# LoraRFM.net
KiCad netlist of a schematic drawn in Altium Designer
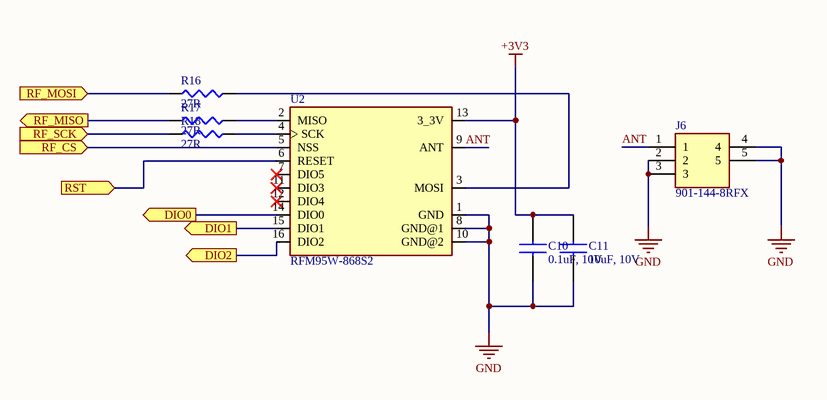
[diagram p0: LoraRFM.SchDoc]

(export (version "E")
  (design (tool "Eeschema 10.0.6"))
  (components
    (comp (ref "C10")
      (value "0.1uF, 10V")
      (footprint "SamacSys:CAPC1608X90N")
      (description "CAP CER 0.1UF 10V X7R 0603")
      (fields
        (field (name "MANUFACTURER_PART_NUMBER") "C0603C104K8RACTU")
        (field (name "MOUSER PART NUMBER") "187-CL10A106MP8NNNC")
      )
      (libsource (lib "SchlibpolyESP") (part "C0603C104K8RACTU"))
    )
    (comp (ref "C11")
      (value "10uF, 10V")
      (footprint "SamacSys:CAPC1608X90N")
      (description "CAP CER 10UF 10V X5R 0603")
      (fields
        (field (name "MANUFACTURER_PART_NUMBER") "CL10A106MP8NNNC")
        (field (name "MOUSER PART NUMBER") "187-CL10A106MP8NNNC")
      )
      (libsource (lib "SchlibpolyESP") (part "CL10A106MP8NNNC"))
    )
    (comp (ref "J6")
      (value "901-144-8RFX")
      (footprint "SamacSys:9011448RFX")
      (description "Connector")
      (fields (field (name "MOUSER PART NUMBER") "523-901-144-8RFX"))
      (libsource (lib "*") (part "901-144-8RFX"))
    )
    (comp (ref "R16")
      (value "27R")
      (footprint "RESC1607X60N")
      (description "RES 27 OHM 5% 1/10W 0603")
      (fields
        (field (name "MANUFACTURER") "Yageo")
        (field (name "MANUFACTURER PART NUMBER") "RC0603JR-0727RL")
      )
      (libsource (lib "SchlibpolyESP") (part "RC0603JR-0727RL"))
    )
    (comp (ref "R17")
      (value "27R")
      (footprint "RESC1607X60N")
      (description "RES 27 OHM 5% 1/10W 0603")
      (fields
        (field (name "MANUFACTURER") "Yageo")
        (field (name "MANUFACTURER PART NUMBER") "RC0603JR-0727RL")
      )
      (libsource (lib "SchlibpolyESP") (part "RC0603JR-0727RL"))
    )
    (comp (ref "R18")
      (value "27R")
      (footprint "RESC1607X60N")
      (description "RES 27 OHM 5% 1/10W 0603")
      (fields
        (field (name "MANUFACTURER") "Yageo")
        (field (name "MANUFACTURER PART NUMBER") "RC0603JR-0727RL")
      )
      (libsource (lib "SchlibpolyESP") (part "RC0603JR-0727RL"))
    )
    (comp (ref "U2")
      (value "RFM95W-868S2")
      (footprint "XCVR_RFM95W-868S2")
      (description "General ISM < 1GHz LoRaâ„¢ Transceiver Module 868MHz Antenna Not Included Surface Mount")
      (fields (field (name "MF") "RF"))
      (libsource (lib "SchlibpolyESP") (part "RFM95W-868S2"))
    )
  )
  (nets
    (net (code "1") (name "+3V3") (class "Default")
      (node (ref "C10") (pin "2") (pinfunction "2_2") (pintype "passive"))
      (node (ref "C11") (pin "2") (pinfunction "2_2") (pintype "passive"))
      (node (ref "U2") (pin "13") (pinfunction "3_3V_13") (pintype "power_in"))
    )
    (net (code "2") (name "/ANT") (class "Default")
      (node (ref "J6") (pin "1") (pinfunction "1_1") (pintype "passive"))
      (node (ref "U2") (pin "9") (pinfunction "ANT_9") (pintype "passive"))
    )
    (net (code "3") (name "/DIO0") (class "Default")
      (node (ref "U2") (pin "14") (pinfunction "DIO0_14") (pintype "passive"))
    )
    (net (code "4") (name "/DIO1") (class "Default")
      (node (ref "U2") (pin "15") (pinfunction "DIO1_15") (pintype "passive"))
    )
    (net (code "5") (name "/DIO2") (class "Default")
      (node (ref "U2") (pin "16") (pinfunction "DIO2_16") (pintype "passive"))
    )
    (net (code "6") (name "/RF_CS") (class "Default")
      (node (ref "U2") (pin "5") (pinfunction "NSS_5") (pintype "passive"))
    )
    (net (code "7") (name "/RF_MISO") (class "Default")
      (node (ref "R17") (pin "1") (pinfunction "1_1") (pintype "passive"))
    )
    (net (code "8") (name "/RF_MOSI") (class "Default")
      (node (ref "R16") (pin "1") (pinfunction "1_1") (pintype "passive"))
    )
    (net (code "9") (name "/RF_SCK") (class "Default")
      (node (ref "R18") (pin "1") (pinfunction "1_1") (pintype "passive"))
    )
    (net (code "10") (name "/RST") (class "Default")
      (node (ref "U2") (pin "6") (pinfunction "RESET_6") (pintype "passive"))
    )
    (net (code "11") (name "GND") (class "Default")
      (node (ref "C10") (pin "1") (pinfunction "1_1") (pintype "passive"))
      (node (ref "C11") (pin "1") (pinfunction "1_1") (pintype "passive"))
      (node (ref "J6") (pin "2") (pinfunction "2_2") (pintype "passive"))
      (node (ref "J6") (pin "3") (pinfunction "3_3") (pintype "passive"))
      (node (ref "J6") (pin "4") (pinfunction "4_4") (pintype "passive"))
      (node (ref "J6") (pin "5") (pinfunction "5_5") (pintype "passive"))
      (node (ref "U2") (pin "1") (pinfunction "GND_1") (pintype "power_in"))
      (node (ref "U2") (pin "10") (pinfunction "GND@2_10") (pintype "power_in"))
      (node (ref "U2") (pin "8") (pinfunction "GND@1_8") (pintype "power_in"))
    )
    (net (code "12") (name "Net-(U2-MISO)") (class "Default")
      (node (ref "R17") (pin "2") (pinfunction "2_2") (pintype "passive"))
      (node (ref "U2") (pin "2") (pinfunction "MISO_2") (pintype "passive"))
    )
    (net (code "13") (name "Net-(U2-MOSI)") (class "Default")
      (node (ref "R16") (pin "2") (pinfunction "2_2") (pintype "passive"))
      (node (ref "U2") (pin "3") (pinfunction "MOSI_3") (pintype "passive"))
    )
    (net (code "14") (name "Net-(U2-SCK)") (class "Default")
      (node (ref "R18") (pin "2") (pinfunction "2_2") (pintype "passive"))
      (node (ref "U2") (pin "4") (pinfunction "SCK_4") (pintype "passive"))
    )
    (net (code "15") (name "unconnected-(U2-DIO3-Pad11)") (class "Default")
      (node (ref "U2") (pin "11") (pinfunction "DIO3_11") (pintype "passive+no_connect"))
    )
    (net (code "16") (name "unconnected-(U2-DIO4-Pad12)") (class "Default")
      (node (ref "U2") (pin "12") (pinfunction "DIO4_12") (pintype "passive+no_connect"))
    )
    (net (code "17") (name "unconnected-(U2-DIO5-Pad7)") (class "Default")
      (node (ref "U2") (pin "7") (pinfunction "DIO5_7") (pintype "passive+no_connect"))
    )
  )
)
